# state-sequencer-v0_1.net
KiCad netlist of a schematic drawn in EAGLE
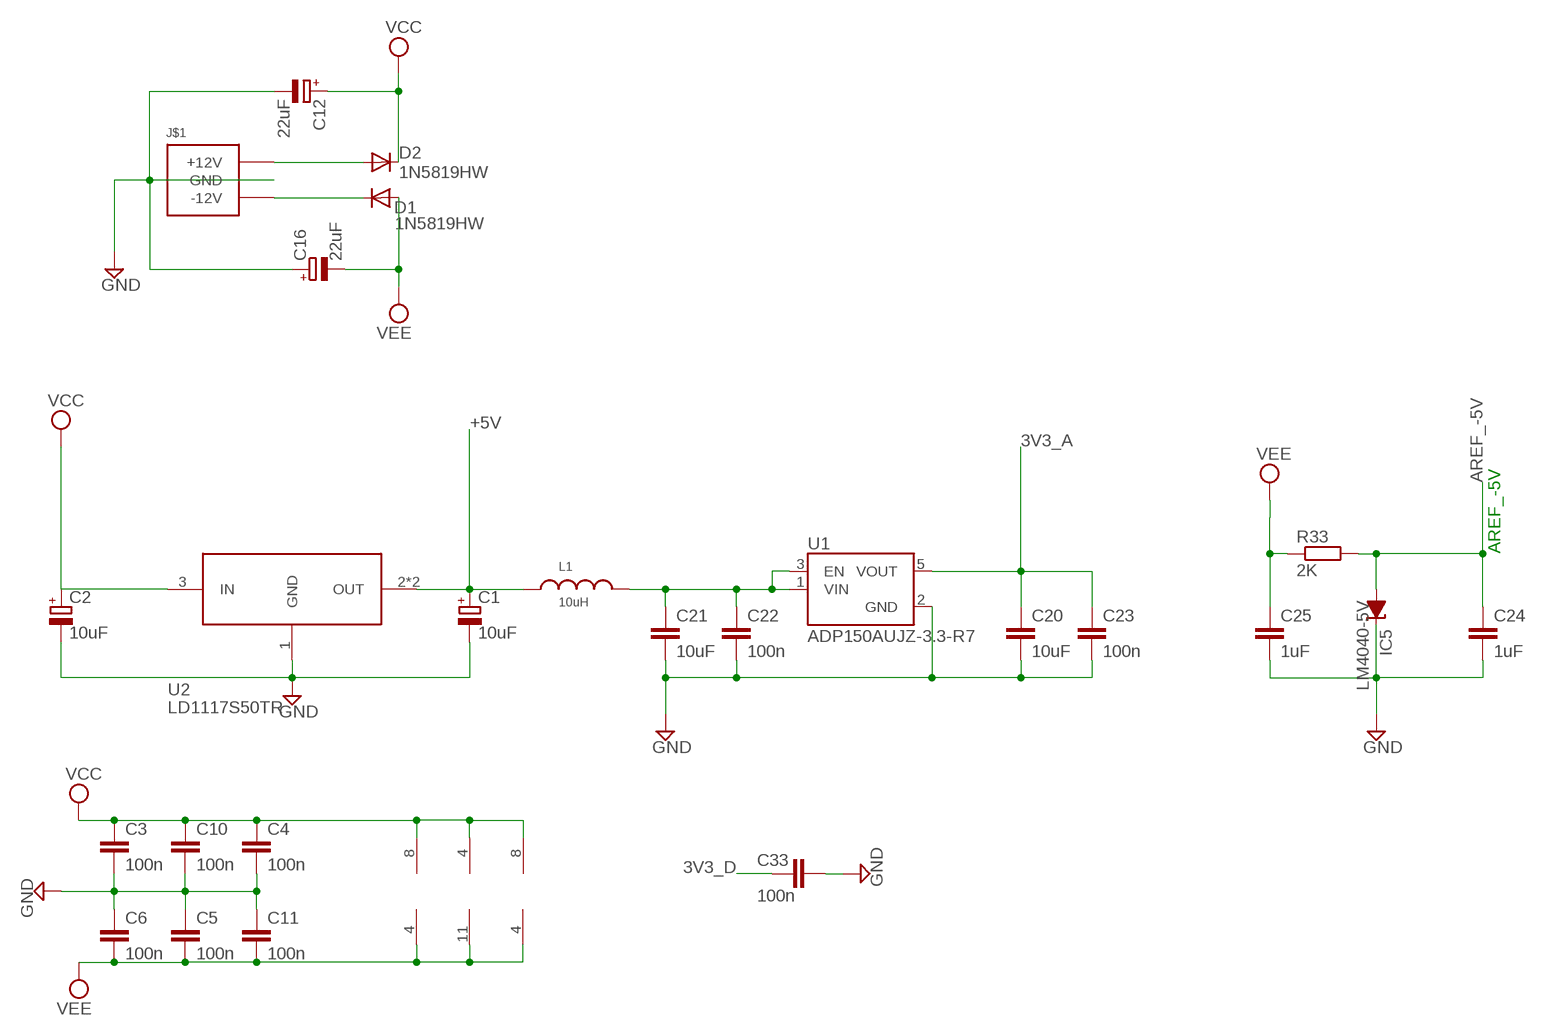
[diagram p0: schematic, sheet 1]
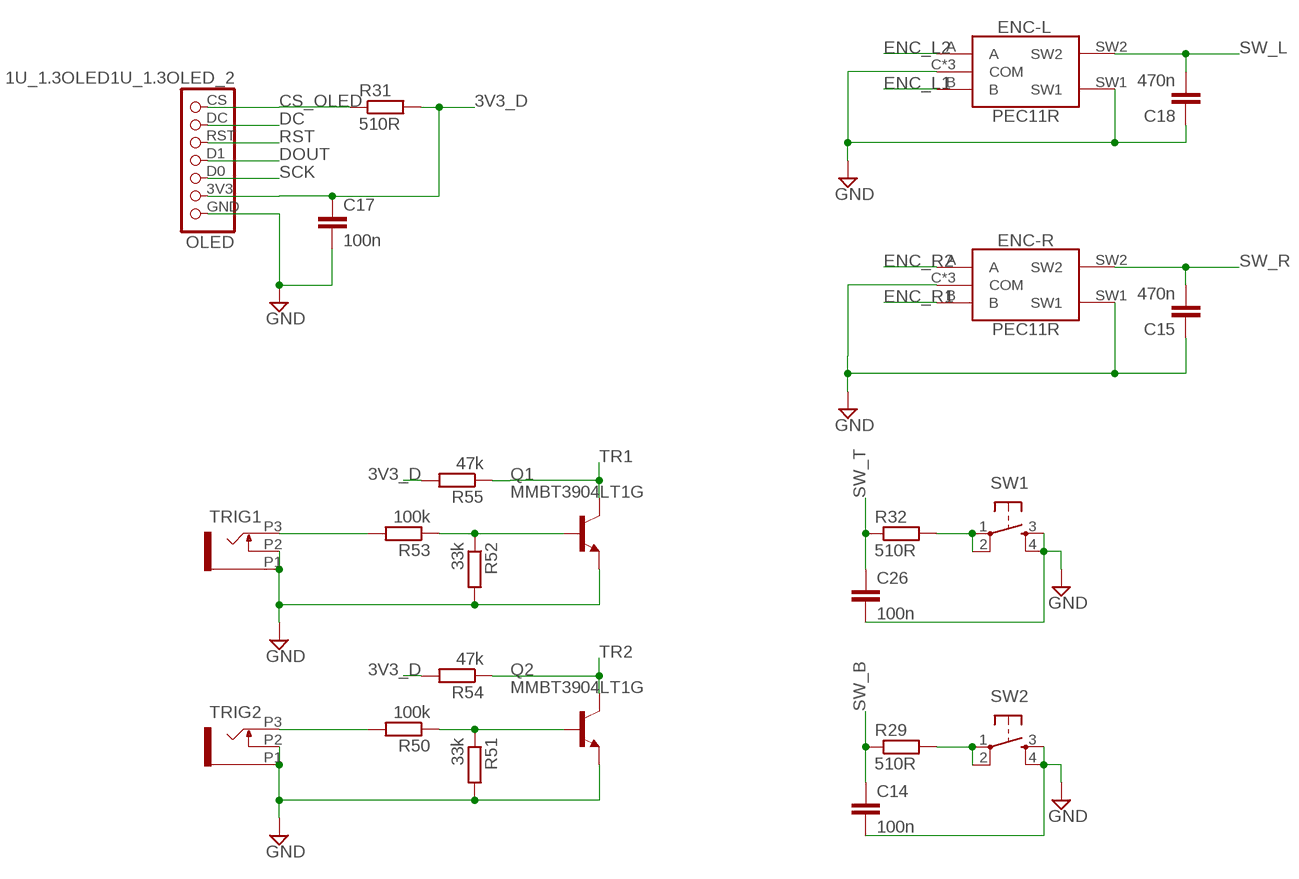
[diagram p1: schematic, sheet 2]

(export (version "E")
  (design (tool "Eeschema 10.0.6"))
  (components
    (comp (ref "C14")
      (value "100n")
      (footprint "eagle-import:C0603")
      (libsource (lib "eagle-import") (part "C-EUC0603"))
    )
    (comp (ref "C15")
      (value "470n")
      (footprint "eagle-import:C0603")
      (libsource (lib "eagle-import") (part "C-EUC0603"))
    )
    (comp (ref "C17")
      (value "100n")
      (footprint "eagle-import:C0603")
      (libsource (lib "eagle-import") (part "C-EUC0603"))
    )
    (comp (ref "C18")
      (value "470n")
      (footprint "eagle-import:C0603")
      (libsource (lib "eagle-import") (part "C-EUC0603"))
    )
    (comp (ref "C26")
      (value "100n")
      (footprint "eagle-import:C0603")
      (libsource (lib "eagle-import") (part "C-EUC0603"))
    )
    (comp (ref "ENC-L")
      (value "PEC11R")
      (footprint "eagle-import:PEC11R-4XXXK-SXXXX")
      (fields
        (field (name "ARROW_PART_NUMBER") "PEC11R-4215K-S0024")
        (field (name "RS_PART_NUMBER") "1674651")
      )
      (libsource (lib "eagle-import") (part "PEC11R"))
    )
    (comp (ref "ENC-R")
      (value "PEC11R")
      (footprint "eagle-import:PEC11R-4XXXK-SXXXX")
      (fields
        (field (name "ARROW_PART_NUMBER") "PEC11R-4215K-S0024")
        (field (name "RS_PART_NUMBER") "1674651")
      )
      (libsource (lib "eagle-import") (part "PEC11R"))
    )
    (comp (ref "OLED")
      (value "1U_1.3OLED1U_1.3OLED_2")
      (footprint "eagle-import:1U_1.3OLED_2")
      (libsource (lib "eagle-import") (part "1U_1.3OLED1U_1.3OLED_2"))
    )
    (comp (ref "Q1")
      (value "MMBT3904LT1G")
      (footprint "eagle-import:TRANSISTOR_SOT23-BEC")
      (libsource (lib "eagle-import") (part "TRANSISTOR_-NPN-SOT23-BECMMBT3904LT1"))
    )
    (comp (ref "Q2")
      (value "MMBT3904LT1G")
      (footprint "eagle-import:TRANSISTOR_SOT23-BEC")
      (libsource (lib "eagle-import") (part "TRANSISTOR_-NPN-SOT23-BECMMBT3904LT1"))
    )
    (comp (ref "R29")
      (value "510R")
      (footprint "eagle-import:R0603")
      (libsource (lib "eagle-import") (part "R-EU_R0603"))
    )
    (comp (ref "R31")
      (value "510R")
      (footprint "eagle-import:R0603")
      (libsource (lib "eagle-import") (part "R-EU_R0603"))
    )
    (comp (ref "R32")
      (value "510R")
      (footprint "eagle-import:R0603")
      (libsource (lib "eagle-import") (part "R-EU_R0603"))
    )
    (comp (ref "R50")
      (value "100k")
      (footprint "eagle-import:R0603")
      (libsource (lib "eagle-import") (part "R-EU_R0603"))
    )
    (comp (ref "R51")
      (value "33k")
      (footprint "eagle-import:R0603")
      (libsource (lib "eagle-import") (part "R-EU_R0603"))
    )
    (comp (ref "R52")
      (value "33k")
      (footprint "eagle-import:R0603")
      (libsource (lib "eagle-import") (part "R-EU_R0603"))
    )
    (comp (ref "R53")
      (value "100k")
      (footprint "eagle-import:R0603")
      (libsource (lib "eagle-import") (part "R-EU_R0603"))
    )
    (comp (ref "R54")
      (value "47k")
      (footprint "eagle-import:R0603")
      (libsource (lib "eagle-import") (part "R-EU_R0603"))
    )
    (comp (ref "R55")
      (value "47k")
      (footprint "eagle-import:R0603")
      (libsource (lib "eagle-import") (part "R-EU_R0603"))
    )
    (comp (ref "SW1")
      (value "TAC_SWITCHPTH")
      (footprint "eagle-import:TACTILE-PTH")
      (libsource (lib "eagle-import") (part "TAC_SWITCHPTH"))
    )
    (comp (ref "SW2")
      (value "TAC_SWITCHPTH")
      (footprint "eagle-import:TACTILE-PTH")
      (libsource (lib "eagle-import") (part "TAC_SWITCHPTH"))
    )
    (comp (ref "TRIG1")
      (value "OG-PJ301_PJ301_THONKICONN")
      (footprint "eagle-import:OG-PJ301_WQP_PJ_301M6_NO_HOLE")
      (libsource (lib "eagle-import") (part "OG-PJ301_PJ301_THONKICONN"))
    )
    (comp (ref "TRIG2")
      (value "OG-PJ301_PJ301_THONKICONN")
      (footprint "eagle-import:OG-PJ301_WQP_PJ_301M6_NO_HOLE")
      (libsource (lib "eagle-import") (part "OG-PJ301_PJ301_THONKICONN"))
    )
    (comp (ref "C1")
      (value "10uF")
      (footprint "eagle-import:PANASONIC_B")
      (libsource (lib "eagle-import") (part "CPOL-EUB"))
    )
    (comp (ref "C2")
      (value "10uF")
      (footprint "eagle-import:PANASONIC_B")
      (libsource (lib "eagle-import") (part "CPOL-EUB"))
    )
    (comp (ref "C3")
      (value "100n")
      (footprint "eagle-import:C0603")
      (libsource (lib "eagle-import") (part "C-EUC0603"))
    )
    (comp (ref "C4")
      (value "100n")
      (footprint "eagle-import:C0603")
      (libsource (lib "eagle-import") (part "C-EUC0603"))
    )
    (comp (ref "C5")
      (value "100n")
      (footprint "eagle-import:C0603")
      (libsource (lib "eagle-import") (part "C-EUC0603"))
    )
    (comp (ref "C6")
      (value "100n")
      (footprint "eagle-import:C0603")
      (libsource (lib "eagle-import") (part "C-EUC0603"))
    )
    (comp (ref "C10")
      (value "100n")
      (footprint "eagle-import:C0603")
      (libsource (lib "eagle-import") (part "C-EUC0603"))
    )
    (comp (ref "C11")
      (value "100n")
      (footprint "eagle-import:C0603")
      (libsource (lib "eagle-import") (part "C-EUC0603"))
    )
    (comp (ref "C12")
      (value "22uF")
      (footprint "eagle-import:PANASONIC_C")
      (libsource (lib "eagle-import") (part "CPOL-EUC"))
    )
    (comp (ref "C16")
      (value "22uF")
      (footprint "eagle-import:PANASONIC_C")
      (libsource (lib "eagle-import") (part "CPOL-EUC"))
    )
    (comp (ref "C20")
      (value "10uF")
      (footprint "eagle-import:C1206K")
      (libsource (lib "eagle-import") (part "C-EUC1206K"))
    )
    (comp (ref "C21")
      (value "10uF")
      (footprint "eagle-import:C1206K")
      (libsource (lib "eagle-import") (part "C-EUC1206K"))
    )
    (comp (ref "C22")
      (value "100n")
      (footprint "eagle-import:C0603")
      (libsource (lib "eagle-import") (part "C-EUC0603"))
    )
    (comp (ref "C23")
      (value "100n")
      (footprint "eagle-import:C0603")
      (libsource (lib "eagle-import") (part "C-EUC0603"))
    )
    (comp (ref "C24")
      (value "1uF")
      (footprint "eagle-import:C0603")
      (libsource (lib "eagle-import") (part "C-EUC0603"))
    )
    (comp (ref "C25")
      (value "1uF")
      (footprint "eagle-import:C0603")
      (libsource (lib "eagle-import") (part "C-EUC0603"))
    )
    (comp (ref "C33")
      (value "100n")
      (footprint "eagle-import:C0603")
      (libsource (lib "eagle-import") (part "C-EUC0603"))
    )
    (comp (ref "D1")
      (value "1N5819HW")
      (footprint "eagle-import:DIODE_SOD123")
      (libsource (lib "eagle-import") (part "DIODE_DIODE-SOD123"))
    )
    (comp (ref "D2")
      (value "1N5819HW")
      (footprint "eagle-import:DIODE_SOD123")
      (libsource (lib "eagle-import") (part "DIODE_DIODE-SOD123"))
    )
    (comp (ref "IC1")
      (value "TL072D")
      (footprint "eagle-import:SO08")
      (libsource (lib "eagle-import") (part "TL072D"))
    )
    (comp (ref "IC2")
      (value "TL072D")
      (footprint "eagle-import:SO08")
      (libsource (lib "eagle-import") (part "TL072D"))
    )
    (comp (ref "IC3")
      (value "TL074D")
      (footprint "eagle-import:SO14")
      (libsource (lib "eagle-import") (part "TL074D"))
    )
    (comp (ref "IC5")
      (value "LM4040-5V")
      (footprint "eagle-import:DBZ_R-PDSO-G3")
      (fields (field (name "MPN") "LM4041B12IDBZR"))
      (libsource (lib "eagle-import") (part "LM4041DBZB12"))
    )
    (comp (ref "J$1")
      (value "POWER_SIMPLE10")
      (footprint "eagle-import:POWER_10")
      (libsource (lib "eagle-import") (part "POWER_SIMPLE10"))
    )
    (comp (ref "L1")
      (value "10uH")
      (footprint "eagle-import:WE-LQ_M")
      (libsource (lib "eagle-import") (part "WE-LQ_1210_744032001"))
    )
    (comp (ref "R33")
      (value "2K")
      (footprint "eagle-import:R0603")
      (libsource (lib "eagle-import") (part "R-EU_R0603"))
    )
    (comp (ref "U1")
      (value "ADP150AUJZ-3.3-R7")
      (footprint "eagle-import:SOT95P280X100-5N")
      (fields (field (name "MF") "Analog Devices") (field (name "MP") "ADP150AUJZ-2.0-R7"))
      (libsource (lib "eagle-import") (part "ADP150AUJZ-3.3-R7"))
    )
    (comp (ref "U2")
      (value "LD1117S50TR")
      (footprint "eagle-import:SOT223")
      (fields (field (name "MF") "STMicroelectronics"))
      (libsource (lib "eagle-import") (part "LD1117S50TR"))
    )
  )
  (nets
    (net (code "1") (name "+5V") (class "Default")
      (node (ref "C1") (pin "+") (pinfunction "+_+") (pintype "passive"))
      (node (ref "L1") (pin "1") (pinfunction "1_1") (pintype "passive"))
      (node (ref "U2") (pin "2") (pinfunction "OUT_2") (pintype "output"))
      (node (ref "U2") (pin "4") (pinfunction "OUT_4") (pintype "output"))
    )
    (net (code "2") (name "3V3_A") (class "Default")
      (node (ref "C20") (pin "1") (pinfunction "1_1") (pintype "passive"))
      (node (ref "C23") (pin "1") (pinfunction "1_1") (pintype "passive"))
      (node (ref "U1") (pin "5") (pinfunction "VOUT_5") (pintype "output"))
    )
    (net (code "3") (name "3V3_D") (class "Default")
      (node (ref "C17") (pin "1") (pinfunction "1_1") (pintype "passive"))
      (node (ref "C33") (pin "2") (pinfunction "2_2") (pintype "passive"))
      (node (ref "OLED") (pin "3V3") (pinfunction "3V3_3V3") (pintype "passive"))
      (node (ref "R31") (pin "2") (pinfunction "2_2") (pintype "passive"))
      (node (ref "R54") (pin "2") (pinfunction "2_2") (pintype "passive"))
      (node (ref "R55") (pin "2") (pinfunction "2_2") (pintype "passive"))
    )
    (net (code "4") (name "AREF_-5V") (class "Default")
      (node (ref "C24") (pin "1") (pinfunction "1_1") (pintype "passive"))
      (node (ref "IC5") (pin "2") (pinfunction "A_2") (pintype "passive"))
      (node (ref "R33") (pin "2") (pinfunction "2_2") (pintype "passive"))
    )
    (net (code "5") (name "CS_OLED") (class "Default")
      (node (ref "OLED") (pin "CS") (pinfunction "CS_CS") (pintype "passive"))
      (node (ref "R31") (pin "1") (pinfunction "1_1") (pintype "passive"))
    )
    (net (code "6") (name "DC") (class "Default")
      (node (ref "OLED") (pin "DC") (pinfunction "DC_DC") (pintype "passive"))
    )
    (net (code "7") (name "DOUT") (class "Default")
      (node (ref "OLED") (pin "D1") (pinfunction "D1_D1") (pintype "passive"))
    )
    (net (code "8") (name "ENC_L1") (class "Default")
      (node (ref "ENC-L") (pin "B") (pinfunction "B_B") (pintype "bidirectional"))
    )
    (net (code "9") (name "ENC_L2") (class "Default")
      (node (ref "ENC-L") (pin "A") (pinfunction "A_A") (pintype "bidirectional"))
    )
    (net (code "10") (name "ENC_R1") (class "Default")
      (node (ref "ENC-R") (pin "B") (pinfunction "B_B") (pintype "bidirectional"))
    )
    (net (code "11") (name "ENC_R2") (class "Default")
      (node (ref "ENC-R") (pin "A") (pinfunction "A_A") (pintype "bidirectional"))
    )
    (net (code "12") (name "GND") (class "Default")
      (node (ref "C1") (pin "-") (pinfunction "-_-") (pintype "passive"))
      (node (ref "C10") (pin "2") (pinfunction "2_2") (pintype "passive"))
      (node (ref "C11") (pin "1") (pinfunction "1_1") (pintype "passive"))
      (node (ref "C12") (pin "-") (pinfunction "-_-") (pintype "passive"))
      (node (ref "C14") (pin "2") (pinfunction "2_2") (pintype "passive"))
      (node (ref "C15") (pin "1") (pinfunction "1_1") (pintype "passive"))
      (node (ref "C16") (pin "+") (pinfunction "+_+") (pintype "passive"))
      (node (ref "C17") (pin "2") (pinfunction "2_2") (pintype "passive"))
      (node (ref "C18") (pin "1") (pinfunction "1_1") (pintype "passive"))
      (node (ref "C2") (pin "-") (pinfunction "-_-") (pintype "passive"))
      (node (ref "C20") (pin "2") (pinfunction "2_2") (pintype "passive"))
      (node (ref "C21") (pin "2") (pinfunction "2_2") (pintype "passive"))
      (node (ref "C22") (pin "2") (pinfunction "2_2") (pintype "passive"))
      (node (ref "C23") (pin "2") (pinfunction "2_2") (pintype "passive"))
      (node (ref "C24") (pin "2") (pinfunction "2_2") (pintype "passive"))
      (node (ref "C25") (pin "2") (pinfunction "2_2") (pintype "passive"))
      (node (ref "C26") (pin "2") (pinfunction "2_2") (pintype "passive"))
      (node (ref "C3") (pin "2") (pinfunction "2_2") (pintype "passive"))
      (node (ref "C33") (pin "1") (pinfunction "1_1") (pintype "passive"))
      (node (ref "C4") (pin "2") (pinfunction "2_2") (pintype "passive"))
      (node (ref "C5") (pin "1") (pinfunction "1_1") (pintype "passive"))
      (node (ref "C6") (pin "1") (pinfunction "1_1") (pintype "passive"))
      (node (ref "ENC-L") (pin "C") (pinfunction "COM_C") (pintype "bidirectional"))
      (node (ref "ENC-L") (pin "SH1") (pinfunction "COM_SH1") (pintype "bidirectional"))
      (node (ref "ENC-L") (pin "SH2") (pinfunction "COM_SH2") (pintype "bidirectional"))
      (node (ref "ENC-L") (pin "SW1") (pinfunction "SW1_SW1") (pintype "bidirectional"))
      (node (ref "ENC-R") (pin "C") (pinfunction "COM_C") (pintype "bidirectional"))
      (node (ref "ENC-R") (pin "SH1") (pinfunction "COM_SH1") (pintype "bidirectional"))
      (node (ref "ENC-R") (pin "SH2") (pinfunction "COM_SH2") (pintype "bidirectional"))
      (node (ref "ENC-R") (pin "SW1") (pinfunction "SW1_SW1") (pintype "bidirectional"))
      (node (ref "IC5") (pin "1") (pinfunction "C_1") (pintype "passive"))
      (node (ref "J$1") (pin "3") (pinfunction "GND_3") (pintype "bidirectional"))
      (node (ref "J$1") (pin "4") (pinfunction "GND_4") (pintype "bidirectional"))
      (node (ref "J$1") (pin "5") (pinfunction "GND_5") (pintype "bidirectional"))
      (node (ref "J$1") (pin "6") (pinfunction "GND_6") (pintype "bidirectional"))
      (node (ref "J$1") (pin "7") (pinfunction "GND_7") (pintype "bidirectional"))
      (node (ref "J$1") (pin "8") (pinfunction "GND_8") (pintype "bidirectional"))
      (node (ref "OLED") (pin "GND") (pinfunction "GND_GND") (pintype "passive"))
      (node (ref "Q1") (pin "E") (pinfunction "E_E") (pintype "passive"))
      (node (ref "Q2") (pin "E") (pinfunction "E_E") (pintype "passive"))
      (node (ref "R51") (pin "2") (pinfunction "2_2") (pintype "passive"))
      (node (ref "R52") (pin "2") (pinfunction "2_2") (pintype "passive"))
      (node (ref "SW1") (pin "3") (pinfunction "3_3") (pintype "passive"))
      (node (ref "SW1") (pin "4") (pinfunction "4_4") (pintype "passive"))
      (node (ref "SW2") (pin "3") (pinfunction "3_3") (pintype "passive"))
      (node (ref "SW2") (pin "4") (pinfunction "4_4") (pintype "passive"))
      (node (ref "TRIG1") (pin "P1") (pinfunction "1_P1") (pintype "passive"))
      (node (ref "TRIG1") (pin "P2") (pinfunction "2_P2") (pintype "passive"))
      (node (ref "TRIG2") (pin "P1") (pinfunction "1_P1") (pintype "passive"))
      (node (ref "TRIG2") (pin "P2") (pinfunction "2_P2") (pintype "passive"))
      (node (ref "U1") (pin "2") (pinfunction "GND_2") (pintype "power_in"))
      (node (ref "U2") (pin "1") (pinfunction "GND_1") (pintype "passive"))
    )
    (net (code "13") (name "Net-(D1-PadC)") (class "Default")
      (node (ref "D1") (pin "C") (pinfunction "C_C") (pintype "passive"))
      (node (ref "J$1") (pin "1") (pinfunction "-12V_1") (pintype "bidirectional"))
      (node (ref "J$1") (pin "2") (pinfunction "-12V_2") (pintype "bidirectional"))
    )
    (net (code "14") (name "Net-(D2-PadA)") (class "Default")
      (node (ref "D2") (pin "A") (pinfunction "A_A") (pintype "passive"))
      (node (ref "J$1") (pin "10") (pinfunction "+12V_10") (pintype "bidirectional"))
      (node (ref "J$1") (pin "9") (pinfunction "+12V_9") (pintype "bidirectional"))
    )
    (net (code "15") (name "Net-(Q1-PadB)") (class "Default")
      (node (ref "Q1") (pin "B") (pinfunction "B_B") (pintype "passive"))
      (node (ref "R52") (pin "1") (pinfunction "1_1") (pintype "passive"))
      (node (ref "R53") (pin "1") (pinfunction "1_1") (pintype "passive"))
    )
    (net (code "16") (name "Net-(Q2-PadB)") (class "Default")
      (node (ref "Q2") (pin "B") (pinfunction "B_B") (pintype "passive"))
      (node (ref "R50") (pin "1") (pinfunction "1_1") (pintype "passive"))
      (node (ref "R51") (pin "1") (pinfunction "1_1") (pintype "passive"))
    )
    (net (code "17") (name "Net-(R29-Pad2)") (class "Default")
      (node (ref "R29") (pin "2") (pinfunction "2_2") (pintype "passive"))
      (node (ref "SW2") (pin "1") (pinfunction "1_1") (pintype "passive"))
      (node (ref "SW2") (pin "2") (pinfunction "2_2") (pintype "passive"))
    )
    (net (code "18") (name "Net-(R32-Pad2)") (class "Default")
      (node (ref "R32") (pin "2") (pinfunction "2_2") (pintype "passive"))
      (node (ref "SW1") (pin "1") (pinfunction "1_1") (pintype "passive"))
      (node (ref "SW1") (pin "2") (pinfunction "2_2") (pintype "passive"))
    )
    (net (code "19") (name "Net-(TRIG1-3)") (class "Default")
      (node (ref "R53") (pin "2") (pinfunction "2_2") (pintype "passive"))
      (node (ref "TRIG1") (pin "P3") (pinfunction "3_P3") (pintype "passive"))
    )
    (net (code "20") (name "Net-(TRIG2-3)") (class "Default")
      (node (ref "R50") (pin "2") (pinfunction "2_2") (pintype "passive"))
      (node (ref "TRIG2") (pin "P3") (pinfunction "3_P3") (pintype "passive"))
    )
    (net (code "21") (name "Net-(U1-EN)") (class "Default")
      (node (ref "C21") (pin "1") (pinfunction "1_1") (pintype "passive"))
      (node (ref "C22") (pin "1") (pinfunction "1_1") (pintype "passive"))
      (node (ref "L1") (pin "2") (pinfunction "2_2") (pintype "passive"))
      (node (ref "U1") (pin "1") (pinfunction "VIN_1") (pintype "input"))
      (node (ref "U1") (pin "3") (pinfunction "EN_3") (pintype "input"))
    )
    (net (code "22") (name "RST") (class "Default")
      (node (ref "OLED") (pin "RST") (pinfunction "RST_RST") (pintype "passive"))
    )
    (net (code "23") (name "SCK") (class "Default")
      (node (ref "OLED") (pin "D0") (pinfunction "D0_D0") (pintype "passive"))
    )
    (net (code "24") (name "SW_B") (class "Default")
      (node (ref "C14") (pin "1") (pinfunction "1_1") (pintype "passive"))
      (node (ref "R29") (pin "1") (pinfunction "1_1") (pintype "passive"))
    )
    (net (code "25") (name "SW_L") (class "Default")
      (node (ref "C18") (pin "2") (pinfunction "2_2") (pintype "passive"))
      (node (ref "ENC-L") (pin "SW2") (pinfunction "SW2_SW2") (pintype "bidirectional"))
    )
    (net (code "26") (name "SW_R") (class "Default")
      (node (ref "C15") (pin "2") (pinfunction "2_2") (pintype "passive"))
      (node (ref "ENC-R") (pin "SW2") (pinfunction "SW2_SW2") (pintype "bidirectional"))
    )
    (net (code "27") (name "SW_T") (class "Default")
      (node (ref "C26") (pin "1") (pinfunction "1_1") (pintype "passive"))
      (node (ref "R32") (pin "1") (pinfunction "1_1") (pintype "passive"))
    )
    (net (code "28") (name "TR1") (class "Default")
      (node (ref "Q1") (pin "C") (pinfunction "C_C") (pintype "passive"))
      (node (ref "R55") (pin "1") (pinfunction "1_1") (pintype "passive"))
    )
    (net (code "29") (name "TR2") (class "Default")
      (node (ref "Q2") (pin "C") (pinfunction "C_C") (pintype "passive"))
      (node (ref "R54") (pin "1") (pinfunction "1_1") (pintype "passive"))
    )
    (net (code "30") (name "VCC") (class "Default")
      (node (ref "C10") (pin "1") (pinfunction "1_1") (pintype "passive"))
      (node (ref "C12") (pin "+") (pinfunction "+_+") (pintype "passive"))
      (node (ref "C2") (pin "+") (pinfunction "+_+") (pintype "passive"))
      (node (ref "C3") (pin "1") (pinfunction "1_1") (pintype "passive"))
      (node (ref "C4") (pin "1") (pinfunction "1_1") (pintype "passive"))
      (node (ref "D2") (pin "C") (pinfunction "C_C") (pintype "passive"))
      (node (ref "IC1") (pin "8") (pinfunction "V+_8") (pintype "power_in"))
      (node (ref "IC2") (pin "8") (pinfunction "V+_8") (pintype "power_in"))
      (node (ref "IC3") (pin "4") (pinfunction "V+_4") (pintype "power_in"))
      (node (ref "U2") (pin "3") (pinfunction "IN_3") (pintype "input"))
    )
    (net (code "31") (name "VEE") (class "Default")
      (node (ref "C11") (pin "2") (pinfunction "2_2") (pintype "passive"))
      (node (ref "C16") (pin "-") (pinfunction "-_-") (pintype "passive"))
      (node (ref "C25") (pin "1") (pinfunction "1_1") (pintype "passive"))
      (node (ref "C5") (pin "2") (pinfunction "2_2") (pintype "passive"))
      (node (ref "C6") (pin "2") (pinfunction "2_2") (pintype "passive"))
      (node (ref "D1") (pin "A") (pinfunction "A_A") (pintype "passive"))
      (node (ref "IC1") (pin "4") (pinfunction "V-_4") (pintype "power_in"))
      (node (ref "IC2") (pin "4") (pinfunction "V-_4") (pintype "power_in"))
      (node (ref "IC3") (pin "11") (pinfunction "V-_11") (pintype "power_in"))
      (node (ref "R33") (pin "1") (pinfunction "1_1") (pintype "passive"))
    )
  )
)
